# led_tester_v2.net
KiCad netlist of a schematic drawn in EAGLE
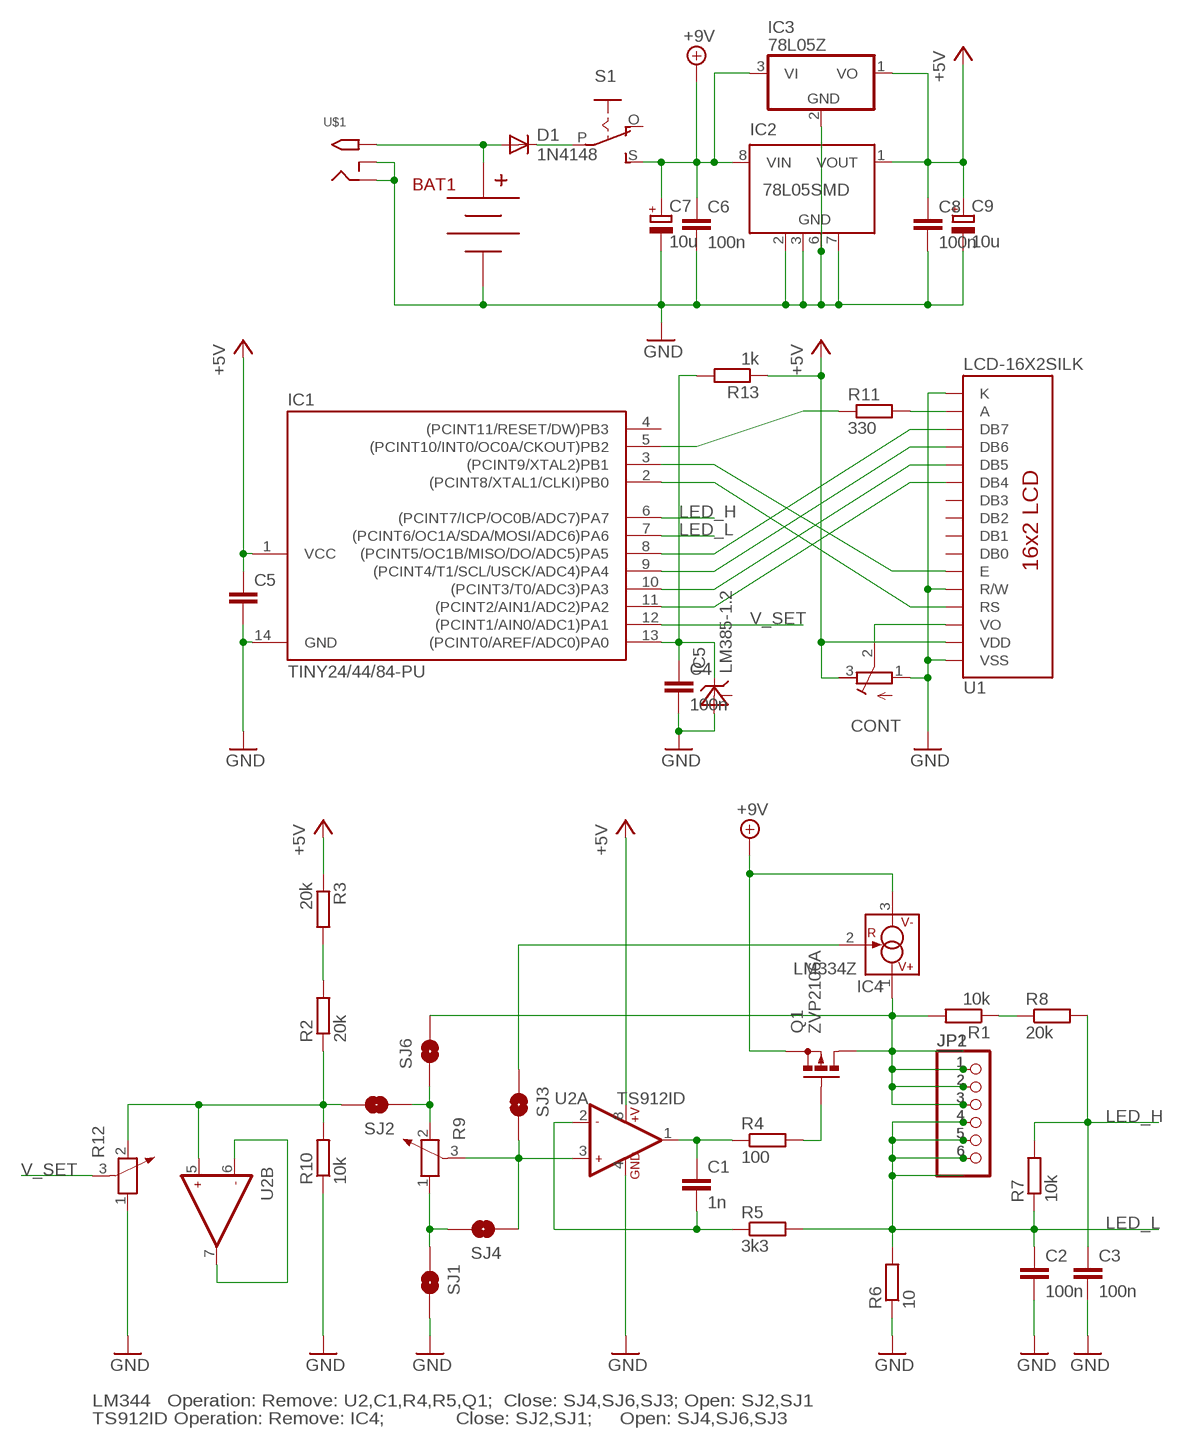
[diagram p0: schematic, sheet 1]

(export (version "E")
  (design (tool "Eeschema 10.0.6"))
  (components
    (comp (ref "BAT1")
      (value "BC9VPCKIT_SOLDERMASK")
      (footprint "eagle-import:BC9VPC_KIT")
      (libsource (lib "eagle-import") (part "BC9VPCKIT_SOLDERMASK"))
    )
    (comp (ref "C1")
      (value "1n")
      (footprint "eagle-import:C025-025X050")
      (libsource (lib "eagle-import") (part "C-EU025-025X050"))
    )
    (comp (ref "C2")
      (value "100n")
      (footprint "eagle-import:C025-025X050")
      (libsource (lib "eagle-import") (part "C-EU025-025X050"))
    )
    (comp (ref "C3")
      (value "100n")
      (footprint "eagle-import:C025-025X050")
      (libsource (lib "eagle-import") (part "C-EU025-025X050"))
    )
    (comp (ref "C4")
      (value "100n")
      (footprint "eagle-import:C025-025X050")
      (libsource (lib "eagle-import") (part "C-EU025-025X050"))
    )
    (comp (ref "C5")
      (value "C-EU025-025X050")
      (footprint "eagle-import:C025-025X050")
      (libsource (lib "eagle-import") (part "C-EU025-025X050"))
    )
    (comp (ref "C6")
      (value "100n")
      (footprint "eagle-import:C025-025X050")
      (libsource (lib "eagle-import") (part "C-EU025-025X050"))
    )
    (comp (ref "C7")
      (value "10u")
      (footprint "eagle-import:E2,5-6E")
      (libsource (lib "eagle-import") (part "CPOL-EUE2,5-6E"))
    )
    (comp (ref "C8")
      (value "100n")
      (footprint "eagle-import:C025-025X050")
      (libsource (lib "eagle-import") (part "C-EU025-025X050"))
    )
    (comp (ref "C9")
      (value "10u")
      (footprint "eagle-import:E2,5-6E")
      (libsource (lib "eagle-import") (part "CPOL-EUE2,5-6E"))
    )
    (comp (ref "CONT")
      (value "R-TRIMM3296P")
      (footprint "eagle-import:RTRIM3296P")
      (libsource (lib "eagle-import") (part "R-TRIMM3296P"))
    )
    (comp (ref "D1")
      (value "1N4148")
      (footprint "eagle-import:D-10")
      (libsource (lib "eagle-import") (part "DIODE-D-10"))
    )
    (comp (ref "IC1")
      (value "TINY24/44/84-PU")
      (footprint "eagle-import:DIL14")
      (libsource (lib "eagle-import") (part "TINY24/44/84-PU"))
    )
    (comp (ref "IC2")
      (value "78L05SMD")
      (footprint "eagle-import:SO08")
      (libsource (lib "eagle-import") (part "78LSMD05"))
    )
    (comp (ref "IC3")
      (value "78L05Z")
      (footprint "eagle-import:TO92")
      (libsource (lib "eagle-import") (part "78ZL05"))
    )
    (comp (ref "IC4")
      (value "LM334Z")
      (footprint "eagle-import:TO92")
      (libsource (lib "eagle-import") (part "LM34Z3"))
    )
    (comp (ref "IC5")
      (value "LM385-1.2")
      (footprint "eagle-import:TO92-")
      (libsource (lib "eagle-import") (part "LM385-1.2"))
    )
    (comp (ref "JP1")
      (value "PINHD-1X6")
      (footprint "eagle-import:1X06")
      (libsource (lib "eagle-import") (part "PINHD-1X6"))
    )
    (comp (ref "JP2")
      (value "PINHD-1X6")
      (footprint "eagle-import:1X06")
      (libsource (lib "eagle-import") (part "PINHD-1X6"))
    )
    (comp (ref "Q1")
      (value "ZVP2106A")
      (footprint "eagle-import:TO92-OVAL")
      (libsource (lib "eagle-import") (part "PFETZVP3306"))
    )
    (comp (ref "R1")
      (value "10k")
      (footprint "eagle-import:0204_7")
      (libsource (lib "eagle-import") (part "R-EU_0204/7"))
    )
    (comp (ref "R2")
      (value "20k")
      (footprint "eagle-import:0204_7")
      (libsource (lib "eagle-import") (part "R-EU_0204/7"))
    )
    (comp (ref "R3")
      (value "20k")
      (footprint "eagle-import:0204_7")
      (libsource (lib "eagle-import") (part "R-EU_0204/7"))
    )
    (comp (ref "R4")
      (value "100")
      (footprint "eagle-import:0204_7")
      (libsource (lib "eagle-import") (part "R-EU_0204/7"))
    )
    (comp (ref "R5")
      (value "3k3")
      (footprint "eagle-import:0204_7")
      (libsource (lib "eagle-import") (part "R-EU_0204/7"))
    )
    (comp (ref "R6")
      (value "10")
      (footprint "eagle-import:0204_7")
      (libsource (lib "eagle-import") (part "R-EU_0204/7"))
    )
    (comp (ref "R7")
      (value "10k")
      (footprint "eagle-import:0204_7")
      (libsource (lib "eagle-import") (part "R-EU_0204/7"))
    )
    (comp (ref "R8")
      (value "20k")
      (footprint "eagle-import:0204_7")
      (libsource (lib "eagle-import") (part "R-EU_0204/7"))
    )
    (comp (ref "R9")
      (value "POTENTIOMETER_PT-10S")
      (footprint "eagle-import:PT-10S")
      (libsource (lib "eagle-import") (part "POTENTIOMETER_PT-10S"))
    )
    (comp (ref "R10")
      (value "10k")
      (footprint "eagle-import:0204_7")
      (libsource (lib "eagle-import") (part "R-EU_0204/7"))
    )
    (comp (ref "R11")
      (value "330")
      (footprint "eagle-import:0204_7")
      (libsource (lib "eagle-import") (part "R-EU_0204/7"))
    )
    (comp (ref "R12")
      (value "POTENTIOMETER_PT-10S")
      (footprint "eagle-import:PT-10S")
      (libsource (lib "eagle-import") (part "POTENTIOMETER_PT-10S"))
    )
    (comp (ref "R13")
      (value "1k")
      (footprint "eagle-import:0204_7")
      (libsource (lib "eagle-import") (part "R-EU_0204/7"))
    )
    (comp (ref "S1")
      (value "EG1218S")
      (footprint "eagle-import:EG1218")
      (libsource (lib "eagle-import") (part "EG1218S"))
    )
    (comp (ref "SJ1")
      (value "SOLDERJUMPERNO")
      (footprint "eagle-import:SJ_2S-NO")
      (libsource (lib "eagle-import") (part "SOLDERJUMPERNO"))
    )
    (comp (ref "SJ2")
      (value "SOLDERJUMPERNO")
      (footprint "eagle-import:SJ_2S-NO")
      (libsource (lib "eagle-import") (part "SOLDERJUMPERNO"))
    )
    (comp (ref "SJ3")
      (value "SOLDERJUMPERNO")
      (footprint "eagle-import:SJ_2S-NO")
      (libsource (lib "eagle-import") (part "SOLDERJUMPERNO"))
    )
    (comp (ref "SJ4")
      (value "SOLDERJUMPERNO")
      (footprint "eagle-import:SJ_2S-NO")
      (libsource (lib "eagle-import") (part "SOLDERJUMPERNO"))
    )
    (comp (ref "SJ6")
      (value "SOLDERJUMPERNO")
      (footprint "eagle-import:SJ_2S-NO")
      (libsource (lib "eagle-import") (part "SOLDERJUMPERNO"))
    )
    (comp (ref "U$1")
      (value "2.1MMJACKTHM")
      (footprint "eagle-import:PJ-102A")
      (libsource (lib "eagle-import") (part "2.1MMJACKTHM"))
    )
    (comp (ref "U1")
      (value "LCD-16X2SILK")
      (footprint "eagle-import:LCD-16X2")
      (libsource (lib "eagle-import") (part "LCD-16X2SILK"))
    )
    (comp (ref "U2")
      (value "TS912ID")
      (footprint "eagle-import:SO08")
      (libsource (lib "eagle-import") (part "LMV358D"))
    )
  )
  (nets
    (net (code "1") (name "+5V") (class "Default")
      (node (ref "C5") (pin "1") (pinfunction "1_1") (pintype "passive"))
      (node (ref "C8") (pin "1") (pinfunction "1_1") (pintype "passive"))
      (node (ref "C9") (pin "+") (pinfunction "+_+") (pintype "passive"))
      (node (ref "CONT") (pin "3") (pinfunction "E_3") (pintype "passive"))
      (node (ref "IC1") (pin "1") (pinfunction "VCC_1") (pintype "power_in"))
      (node (ref "IC2") (pin "1") (pinfunction "VOUT_1") (pintype "output"))
      (node (ref "IC3") (pin "1") (pinfunction "VO_1") (pintype "passive"))
      (node (ref "R13") (pin "1") (pinfunction "1_1") (pintype "passive"))
      (node (ref "R3") (pin "1") (pinfunction "1_1") (pintype "passive"))
      (node (ref "U1") (pin "2") (pinfunction "VDD_2") (pintype "power_in"))
      (node (ref "U2") (pin "8") (pinfunction "+V_8") (pintype "power_in"))
    )
    (net (code "2") (name "+9V") (class "Default")
      (node (ref "C6") (pin "1") (pinfunction "1_1") (pintype "passive"))
      (node (ref "C7") (pin "+") (pinfunction "+_+") (pintype "passive"))
      (node (ref "IC2") (pin "8") (pinfunction "VIN_8") (pintype "passive"))
      (node (ref "IC3") (pin "3") (pinfunction "VI_3") (pintype "input"))
      (node (ref "IC4") (pin "3") (pinfunction "V-_3") (pintype "passive"))
      (node (ref "Q1") (pin "1") (pinfunction "S_1") (pintype "passive"))
      (node (ref "S1") (pin "S") (pinfunction "S_S") (pintype "passive"))
    )
    (net (code "3") (name "/LED_H") (class "Default")
      (node (ref "C3") (pin "1") (pinfunction "1_1") (pintype "passive"))
      (node (ref "IC1") (pin "6") (pinfunction "(PCINT7/ICP/OC0B/ADC7)PA7_6") (pintype "bidirectional"))
      (node (ref "R7") (pin "2") (pinfunction "2_2") (pintype "passive"))
      (node (ref "R8") (pin "2") (pinfunction "2_2") (pintype "passive"))
    )
    (net (code "4") (name "/LED_L") (class "Default")
      (node (ref "C2") (pin "1") (pinfunction "1_1") (pintype "passive"))
      (node (ref "IC1") (pin "7") (pinfunction "(PCINT6/OC1A/SDA/MOSI/ADC6)PA6_7") (pintype "bidirectional"))
      (node (ref "JP1") (pin "4") (pinfunction "4_4") (pintype "passive"))
      (node (ref "JP1") (pin "5") (pinfunction "5_5") (pintype "passive"))
      (node (ref "JP1") (pin "6") (pinfunction "6_6") (pintype "passive"))
      (node (ref "JP2") (pin "4") (pinfunction "4_4") (pintype "passive"))
      (node (ref "JP2") (pin "5") (pinfunction "5_5") (pintype "passive"))
      (node (ref "JP2") (pin "6") (pinfunction "6_6") (pintype "passive"))
      (node (ref "R5") (pin "2") (pinfunction "2_2") (pintype "passive"))
      (node (ref "R6") (pin "2") (pinfunction "2_2") (pintype "passive"))
      (node (ref "R7") (pin "1") (pinfunction "1_1") (pintype "passive"))
    )
    (net (code "5") (name "/V_SET") (class "Default")
      (node (ref "IC1") (pin "12") (pinfunction "(PCINT1/AIN0/ADC1)PA1_12") (pintype "bidirectional"))
      (node (ref "R12") (pin "3") (pinfunction "3_3") (pintype "passive"))
    )
    (net (code "6") (name "GND") (class "Default")
      (node (ref "BAT1") (pin "V+") (pinfunction "V-_V+") (pintype "bidirectional"))
      (node (ref "C2") (pin "2") (pinfunction "2_2") (pintype "passive"))
      (node (ref "C3") (pin "2") (pinfunction "2_2") (pintype "passive"))
      (node (ref "C4") (pin "2") (pinfunction "2_2") (pintype "passive"))
      (node (ref "C5") (pin "2") (pinfunction "2_2") (pintype "passive"))
      (node (ref "C6") (pin "2") (pinfunction "2_2") (pintype "passive"))
      (node (ref "C7") (pin "-") (pinfunction "-_-") (pintype "passive"))
      (node (ref "C8") (pin "2") (pinfunction "2_2") (pintype "passive"))
      (node (ref "C9") (pin "-") (pinfunction "-_-") (pintype "passive"))
      (node (ref "CONT") (pin "1") (pinfunction "A_1") (pintype "passive"))
      (node (ref "IC1") (pin "14") (pinfunction "GND_14") (pintype "power_in"))
      (node (ref "IC2") (pin "2") (pinfunction "GND_2") (pintype "power_in"))
      (node (ref "IC2") (pin "3") (pinfunction "GND_3") (pintype "power_in"))
      (node (ref "IC2") (pin "6") (pinfunction "GND_6") (pintype "power_in"))
      (node (ref "IC2") (pin "7") (pinfunction "GND_7") (pintype "power_in"))
      (node (ref "IC3") (pin "2") (pinfunction "GND_2") (pintype "passive"))
      (node (ref "IC5") (pin "1") (pinfunction "A_1") (pintype "passive"))
      (node (ref "R10") (pin "1") (pinfunction "1_1") (pintype "passive"))
      (node (ref "R12") (pin "1") (pinfunction "1_1") (pintype "passive"))
      (node (ref "R6") (pin "1") (pinfunction "1_1") (pintype "passive"))
      (node (ref "SJ1") (pin "2") (pinfunction "2_2") (pintype "passive"))
      (node (ref "U$1") (pin "RING") (pinfunction "RING_RING") (pintype "bidirectional"))
      (node (ref "U$1") (pin "RING_SW") (pinfunction "RING_SW_RING_SW") (pintype "bidirectional"))
      (node (ref "U1") (pin "1") (pinfunction "VSS_1") (pintype "power_in"))
      (node (ref "U1") (pin "16") (pinfunction "K_16") (pintype "power_in"))
      (node (ref "U1") (pin "5") (pinfunction "R/W_5") (pintype "input"))
      (node (ref "U2") (pin "4") (pinfunction "GND_4") (pintype "power_in"))
    )
    (net (code "7") (name "Net-(BAT1-V+)") (class "Default")
      (node (ref "BAT1") (pin "V-") (pinfunction "V+_V-") (pintype "bidirectional"))
      (node (ref "D1") (pin "A") (pinfunction "A_A") (pintype "passive"))
      (node (ref "U$1") (pin "TIP") (pinfunction "TIP_TIP") (pintype "bidirectional"))
    )
    (net (code "8") (name "Net-(CONT-S)") (class "Default")
      (node (ref "CONT") (pin "2") (pinfunction "S_2") (pintype "passive"))
      (node (ref "U1") (pin "3") (pinfunction "VO_3") (pintype "bidirectional"))
    )
    (net (code "9") (name "Net-(D1-PadC)") (class "Default")
      (node (ref "D1") (pin "C") (pinfunction "C_C") (pintype "passive"))
      (node (ref "S1") (pin "P") (pinfunction "P_P") (pintype "passive"))
    )
    (net (code "10") (name "Net-(IC1-(PCINT0{slash}AREF{slash}ADC0)PA0)") (class "Default")
      (node (ref "C4") (pin "1") (pinfunction "1_1") (pintype "passive"))
      (node (ref "IC1") (pin "13") (pinfunction "(PCINT0/AREF/ADC0)PA0_13") (pintype "bidirectional"))
      (node (ref "IC5") (pin "2") (pinfunction "C_2") (pintype "passive"))
      (node (ref "R13") (pin "2") (pinfunction "2_2") (pintype "passive"))
    )
    (net (code "11") (name "Net-(IC1-(PCINT2{slash}AIN1{slash}ADC2)PA2)") (class "Default")
      (node (ref "IC1") (pin "11") (pinfunction "(PCINT2/AIN1/ADC2)PA2_11") (pintype "bidirectional"))
      (node (ref "U1") (pin "11") (pinfunction "DB4_11") (pintype "bidirectional"))
    )
    (net (code "12") (name "Net-(IC1-(PCINT3{slash}T0{slash}ADC3)PA3)") (class "Default")
      (node (ref "IC1") (pin "10") (pinfunction "(PCINT3/T0/ADC3)PA3_10") (pintype "bidirectional"))
      (node (ref "U1") (pin "12") (pinfunction "DB5_12") (pintype "bidirectional"))
    )
    (net (code "13") (name "Net-(IC1-(PCINT4{slash}T1{slash}SCL{slash}USCK{slash}ADC4)PA4)") (class "Default")
      (node (ref "IC1") (pin "9") (pinfunction "(PCINT4/T1/SCL/USCK/ADC4)PA4_9") (pintype "bidirectional"))
      (node (ref "U1") (pin "13") (pinfunction "DB6_13") (pintype "bidirectional"))
    )
    (net (code "14") (name "Net-(IC1-(PCINT5{slash}OC1B{slash}MISO{slash}DO{slash}ADC5)PA5)") (class "Default")
      (node (ref "IC1") (pin "8") (pinfunction "(PCINT5/OC1B/MISO/DO/ADC5)PA5_8") (pintype "bidirectional"))
      (node (ref "U1") (pin "14") (pinfunction "DB7_14") (pintype "bidirectional"))
    )
    (net (code "15") (name "Net-(IC1-(PCINT8{slash}XTAL1{slash}CLKI)PB0)") (class "Default")
      (node (ref "IC1") (pin "2") (pinfunction "(PCINT8/XTAL1/CLKI)PB0_2") (pintype "bidirectional"))
      (node (ref "U1") (pin "4") (pinfunction "RS_4") (pintype "input"))
    )
    (net (code "16") (name "Net-(IC1-(PCINT9{slash}XTAL2)PB1)") (class "Default")
      (node (ref "IC1") (pin "3") (pinfunction "(PCINT9/XTAL2)PB1_3") (pintype "bidirectional"))
      (node (ref "U1") (pin "6") (pinfunction "E_6") (pintype "input"))
    )
    (net (code "17") (name "Net-(IC1-(PCINT10{slash}INT0{slash}OC0A{slash}CKOUT)PB2)") (class "Default")
      (node (ref "IC1") (pin "5") (pinfunction "(PCINT10/INT0/OC0A/CKOUT)PB2_5") (pintype "bidirectional"))
      (node (ref "R11") (pin "1") (pinfunction "1_1") (pintype "passive"))
    )
    (net (code "18") (name "Net-(IC4-R)") (class "Default")
      (node (ref "IC4") (pin "2") (pinfunction "R_2") (pintype "passive"))
      (node (ref "SJ3") (pin "1") (pinfunction "1_1") (pintype "passive"))
    )
    (net (code "19") (name "Net-(IC4-V+)") (class "Default")
      (node (ref "IC4") (pin "1") (pinfunction "V+_1") (pintype "passive"))
      (node (ref "JP1") (pin "1") (pinfunction "1_1") (pintype "passive"))
      (node (ref "JP1") (pin "2") (pinfunction "2_2") (pintype "passive"))
      (node (ref "JP1") (pin "3") (pinfunction "3_3") (pintype "passive"))
      (node (ref "JP2") (pin "1") (pinfunction "1_1") (pintype "passive"))
      (node (ref "JP2") (pin "2") (pinfunction "2_2") (pintype "passive"))
      (node (ref "JP2") (pin "3") (pinfunction "3_3") (pintype "passive"))
      (node (ref "Q1") (pin "3") (pinfunction "D_3") (pintype "passive"))
      (node (ref "R1") (pin "2") (pinfunction "2_2") (pintype "passive"))
      (node (ref "SJ6") (pin "2") (pinfunction "2_2") (pintype "passive"))
    )
    (net (code "20") (name "Net-(Q1-G)") (class "Default")
      (node (ref "Q1") (pin "2") (pinfunction "G_2") (pintype "passive"))
      (node (ref "R4") (pin "2") (pinfunction "2_2") (pintype "passive"))
    )
    (net (code "21") (name "Net-(R1-Pad1)") (class "Default")
      (node (ref "R1") (pin "1") (pinfunction "1_1") (pintype "passive"))
      (node (ref "R8") (pin "1") (pinfunction "1_1") (pintype "passive"))
    )
    (net (code "22") (name "Net-(R2-Pad2)") (class "Default")
      (node (ref "R2") (pin "2") (pinfunction "2_2") (pintype "passive"))
      (node (ref "R3") (pin "2") (pinfunction "2_2") (pintype "passive"))
    )
    (net (code "23") (name "Net-(R9-Pad1)") (class "Default")
      (node (ref "R9") (pin "1") (pinfunction "1_1") (pintype "passive"))
      (node (ref "SJ1") (pin "1") (pinfunction "1_1") (pintype "passive"))
      (node (ref "SJ4") (pin "2") (pinfunction "2_2") (pintype "passive"))
    )
    (net (code "24") (name "Net-(R9-Pad2)") (class "Default")
      (node (ref "R9") (pin "2") (pinfunction "2_2") (pintype "passive"))
      (node (ref "SJ2") (pin "1") (pinfunction "1_1") (pintype "passive"))
      (node (ref "SJ6") (pin "1") (pinfunction "1_1") (pintype "passive"))
    )
    (net (code "25") (name "Net-(U1-A)") (class "Default")
      (node (ref "R11") (pin "2") (pinfunction "2_2") (pintype "passive"))
      (node (ref "U1") (pin "15") (pinfunction "A_15") (pintype "power_in"))
    )
    (net (code "26") (name "Net-(U2A-+IN1)") (class "Default")
      (node (ref "R9") (pin "3") (pinfunction "3_3") (pintype "passive"))
      (node (ref "SJ3") (pin "2") (pinfunction "2_2") (pintype "passive"))
      (node (ref "SJ4") (pin "1") (pinfunction "1_1") (pintype "passive"))
      (node (ref "U2") (pin "3") (pinfunction "+IN1_3") (pintype "input"))
    )
    (net (code "27") (name "Net-(U2A--IN1)") (class "Default")
      (node (ref "C1") (pin "2") (pinfunction "2_2") (pintype "passive"))
      (node (ref "R5") (pin "1") (pinfunction "1_1") (pintype "passive"))
      (node (ref "U2") (pin "2") (pinfunction "-IN1_2") (pintype "input"))
    )
    (net (code "28") (name "Net-(U2A-OUT1)") (class "Default")
      (node (ref "C1") (pin "1") (pinfunction "1_1") (pintype "passive"))
      (node (ref "R4") (pin "1") (pinfunction "1_1") (pintype "passive"))
      (node (ref "U2") (pin "1") (pinfunction "OUT1_1") (pintype "output"))
    )
    (net (code "29") (name "Net-(U2B-+IN2)") (class "Default")
      (node (ref "R10") (pin "2") (pinfunction "2_2") (pintype "passive"))
      (node (ref "R12") (pin "2") (pinfunction "2_2") (pintype "passive"))
      (node (ref "R2") (pin "1") (pinfunction "1_1") (pintype "passive"))
      (node (ref "SJ2") (pin "2") (pinfunction "2_2") (pintype "passive"))
      (node (ref "U2") (pin "5") (pinfunction "+IN2_5") (pintype "input"))
    )
    (net (code "30") (name "Net-(U2B--IN2)") (class "Default")
      (node (ref "U2") (pin "6") (pinfunction "-IN2_6") (pintype "input"))
      (node (ref "U2") (pin "7") (pinfunction "OUT2_7") (pintype "output"))
    )
    (net (code "31") (name "unconnected-(IC1-(PCINT11{slash}RESET{slash}DW)PB3-Pad4)") (class "Default")
      (node (ref "IC1") (pin "4") (pinfunction "(PCINT11/RESET/DW)PB3_4") (pintype "bidirectional"))
    )
    (net (code "32") (name "unconnected-(IC5-FB-Pad3)") (class "Default")
      (node (ref "IC5") (pin "3") (pinfunction "FB_3") (pintype "passive"))
    )
    (net (code "33") (name "unconnected-(S1-PadO)") (class "Default")
      (node (ref "S1") (pin "O") (pinfunction "O_O") (pintype "passive"))
    )
    (net (code "34") (name "unconnected-(U1-DB0-Pad7)") (class "Default")
      (node (ref "U1") (pin "7") (pinfunction "DB0_7") (pintype "bidirectional"))
    )
    (net (code "35") (name "unconnected-(U1-DB1-Pad8)") (class "Default")
      (node (ref "U1") (pin "8") (pinfunction "DB1_8") (pintype "bidirectional"))
    )
    (net (code "36") (name "unconnected-(U1-DB2-Pad9)") (class "Default")
      (node (ref "U1") (pin "9") (pinfunction "DB2_9") (pintype "bidirectional"))
    )
    (net (code "37") (name "unconnected-(U1-DB3-Pad10)") (class "Default")
      (node (ref "U1") (pin "10") (pinfunction "DB3_10") (pintype "bidirectional"))
    )
  )
)
